# CH32V103R-R0.net
KiCad netlist of a schematic drawn in Altium Designer
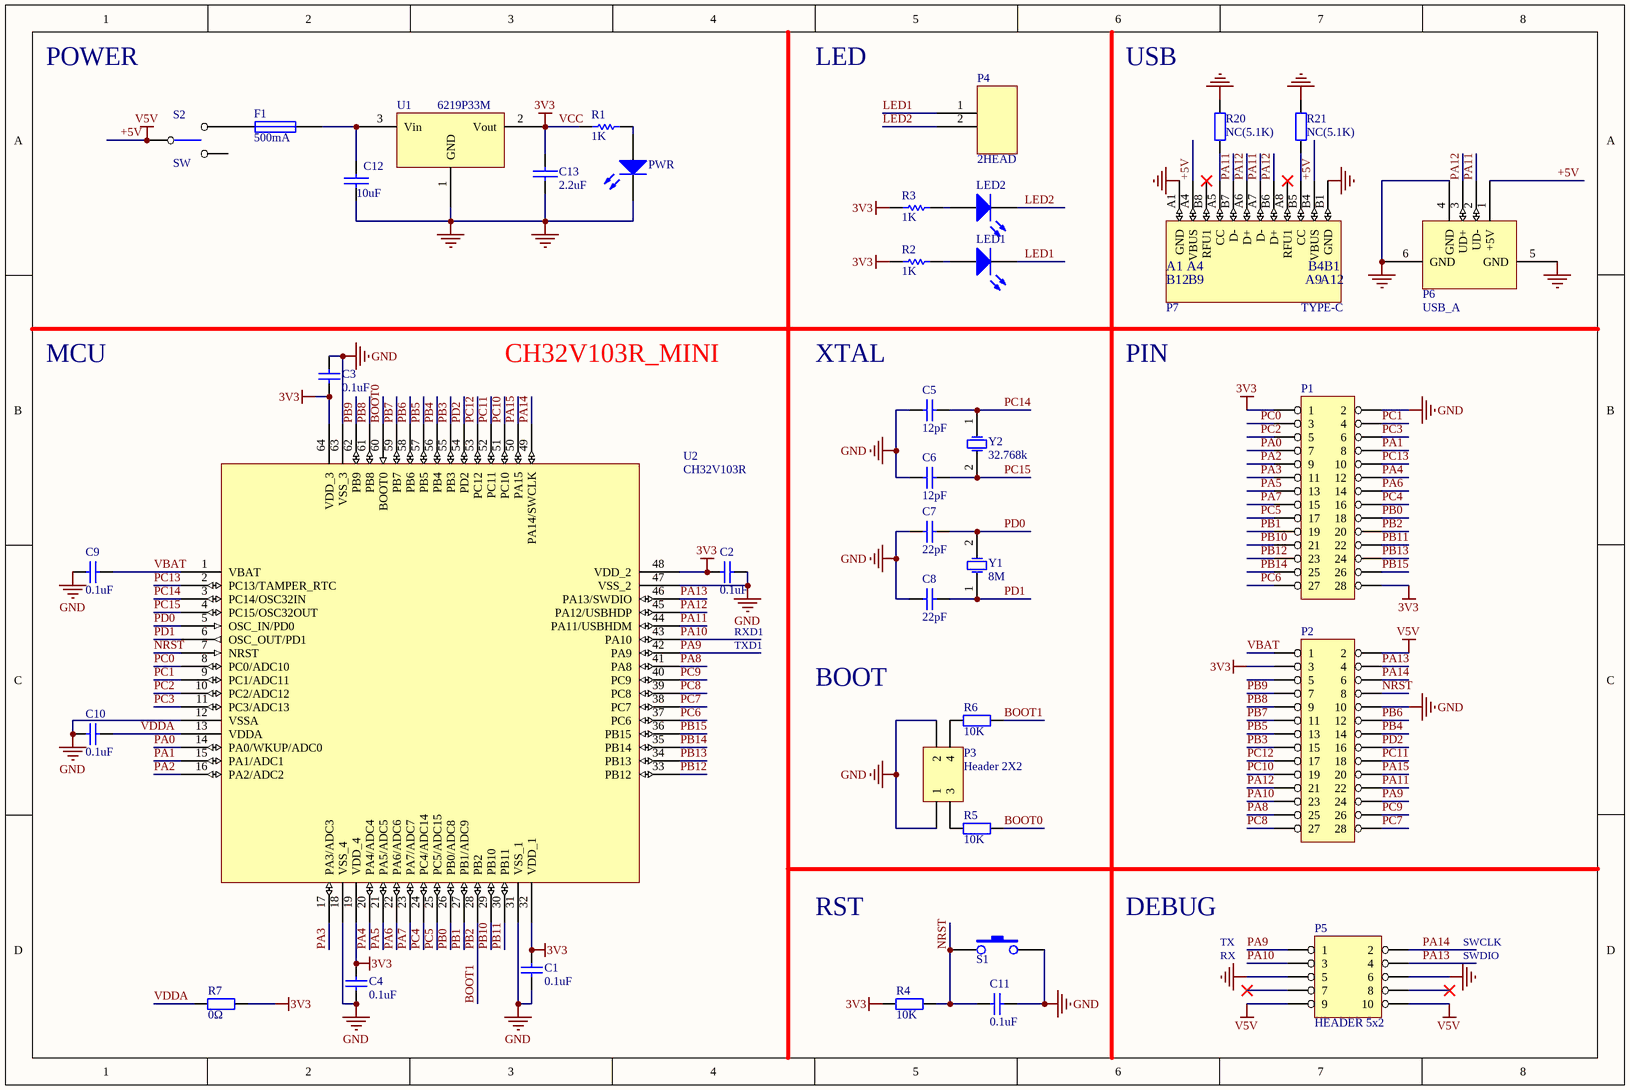
[diagram p0: CH32V103R-R0.SchDoc]

(export (version "E")
  (design (tool "Eeschema 10.0.6"))
  (components
    (comp (ref "C1")
      (value "0.1uF")
      (footprint "0603_C")
      (description "Capacitor")
      (fields (field (name "PUBLISHER") "Altium Limited"))
      (libsource (lib "Miscellaneous Devices") (part "Cap"))
    )
    (comp (ref "C2")
      (value "0.1uF")
      (footprint "0603_C")
      (description "Capacitor")
      (fields (field (name "PUBLISHER") "Altium Limited"))
      (libsource (lib "Miscellaneous Devices") (part "Cap"))
    )
    (comp (ref "C3")
      (value "0.1uF")
      (footprint "0603_C")
      (description "Capacitor")
      (fields (field (name "PUBLISHER") "Altium Limited"))
      (libsource (lib "Miscellaneous Devices") (part "Cap"))
    )
    (comp (ref "C4")
      (value "0.1uF")
      (footprint "0603_C")
      (description "Capacitor")
      (fields (field (name "PUBLISHER") "Altium Limited"))
      (libsource (lib "Miscellaneous Devices") (part "Cap"))
    )
    (comp (ref "C5")
      (value "12pF")
      (footprint "0603_C")
      (description "Capacitor")
      (fields (field (name "PUBLISHER") "Altium Limited"))
      (libsource (lib "Miscellaneous Devices") (part "Cap"))
    )
    (comp (ref "C6")
      (value "12pF")
      (footprint "0603_C")
      (description "Capacitor")
      (fields (field (name "PUBLISHER") "Altium Limited"))
      (libsource (lib "Miscellaneous Devices") (part "Cap"))
    )
    (comp (ref "C7")
      (value "22pF")
      (footprint "0603_C")
      (description "Capacitor")
      (fields (field (name "PUBLISHER") "Altium Limited"))
      (libsource (lib "Miscellaneous Devices") (part "Cap"))
    )
    (comp (ref "C8")
      (value "22pF")
      (footprint "0603_C")
      (description "Capacitor")
      (fields (field (name "PUBLISHER") "Altium Limited"))
      (libsource (lib "Miscellaneous Devices") (part "Cap"))
    )
    (comp (ref "C9")
      (value "0.1uF")
      (footprint "0603_C")
      (description "Capacitor")
      (fields (field (name "PUBLISHER") "Altium Limited"))
      (libsource (lib "Miscellaneous Devices") (part "Cap"))
    )
    (comp (ref "C10")
      (value "0.1uF")
      (footprint "0603_C")
      (description "Capacitor")
      (fields (field (name "PUBLISHER") "Altium Limited"))
      (libsource (lib "Miscellaneous Devices") (part "Cap"))
    )
    (comp (ref "C11")
      (value "0.1uF")
      (footprint "0603_C")
      (description "Capacitor")
      (fields (field (name "PUBLISHER") "Altium Limited"))
      (libsource (lib "Miscellaneous Devices") (part "Cap"))
    )
    (comp (ref "C12")
      (value "10uF")
      (footprint "3216_C")
      (description "Capacitor")
      (libsource (lib "*") (part "CAP"))
    )
    (comp (ref "C13")
      (value "2.2uF")
      (footprint "0603_C")
      (description "Capacitor")
      (libsource (lib "*") (part "CAP"))
    )
    (comp (ref "F1")
      (value "500mA")
      (footprint "0603")
      (description "Fuse")
      (libsource (lib "*") (part "FUSE1"))
    )
    (comp (ref "LED1")
      (value "LED1   blue")
      (footprint "0603+")
      (description "Typical INFRARED GaAs LED")
      (fields (field (name "PUBLISHER") "Altium Limited"))
      (libsource (lib "Miscellaneous Devices") (part "LED0"))
    )
    (comp (ref "LED2")
      (value "LED2  blue")
      (footprint "0603+")
      (description "Typical INFRARED GaAs LED")
      (fields (field (name "PUBLISHER") "Altium Limited"))
      (libsource (lib "Miscellaneous Devices") (part "LED0"))
    )
    (comp (ref "P1")
      (value "HEADER 14x2")
      (footprint "MYPCB:IDC28-2.54MM")
      (description "Header, 14-Pin, Dual row")
      (libsource (lib "wch_sch_others") (part "HEADER 14x2"))
    )
    (comp (ref "P2")
      (value "HEADER 14x2")
      (footprint "MYPCB:IDC28-2.54MM")
      (description "Header, 14-Pin, Dual row")
      (libsource (lib "wch_sch_others") (part "HEADER 14x2"))
    )
    (comp (ref "P3")
      (value "Header 2X2")
      (footprint "IDC4-2.54mm")
      (description "Header, 2-Pin, Dual row")
      (fields (field (name "PUBLISHER") "Altium Limited"))
      (libsource (lib "Miscellaneous Connectors") (part "Header 2X2"))
    )
    (comp (ref "P4") (value "2HEAD") (footprint "SIP2-2.54mm") (libsource (lib "MYSCH") (part "2HEAD")))
    (comp (ref "P5")
      (value "HEADER 5x2")
      (footprint "MYPCB:IDC10-2.54mm")
      (description "Header, 4-Pin, Dual row")
      (libsource (lib "wch_sch_others") (part "HEADER 5x2"))
    )
    (comp (ref "P6")
      (value "USB_A")
      (footprint "USBAF")
      (description "USB Port")
      (libsource (lib "CHXXXSCH") (part "USB"))
    )
    (comp (ref "P7")
      (value "TYPE-C")
      (footprint "TYPE-C-Receptacle-2.0")
      (libsource (lib "*") (part "TYPE-C1"))
    )
    (comp (ref "PWR")
      (value "POWER  red")
      (footprint "0603+")
      (description "Typical INFRARED GaAs LED")
      (fields (field (name "PUBLISHER") "Altium Limited"))
      (libsource (lib "Miscellaneous Devices") (part "LED0"))
    )
    (comp (ref "R1")
      (value "1K")
      (footprint "0603")
      (description "Semiconductor Resistor")
      (fields (field (name "PUBLISHER") "Altium Limited"))
      (libsource (lib "Miscellaneous Devices") (part "Res Semi"))
    )
    (comp (ref "R2")
      (value "1K")
      (footprint "0603")
      (description "Semiconductor Resistor")
      (fields (field (name "PUBLISHER") "Altium Limited"))
      (libsource (lib "Miscellaneous Devices") (part "Res Semi"))
    )
    (comp (ref "R3")
      (value "1K")
      (footprint "0603")
      (description "Semiconductor Resistor")
      (fields (field (name "PUBLISHER") "Altium Limited"))
      (libsource (lib "Miscellaneous Devices") (part "Res Semi"))
    )
    (comp (ref "R4")
      (value "10K")
      (footprint "0603")
      (description "Resistor")
      (fields (field (name "PUBLISHER") "Altium Limited"))
      (libsource (lib "") (part "Res2_1"))
    )
    (comp (ref "R5")
      (value "10K")
      (footprint "0603")
      (description "Resistor")
      (fields (field (name "PUBLISHER") "Altium Limited"))
      (libsource (lib "") (part "Res2_1"))
    )
    (comp (ref "R6")
      (value "10K")
      (footprint "0603")
      (description "Resistor")
      (fields (field (name "PUBLISHER") "Altium Limited"))
      (libsource (lib "") (part "Res2_1"))
    )
    (comp (ref "R7")
      (value "0Ω")
      (footprint "0603")
      (description "Resistor")
      (fields (field (name "PUBLISHER") "Altium Limited"))
      (libsource (lib "") (part "Res2_1"))
    )
    (comp (ref "R20")
      (value "NC(5.1K)")
      (footprint "0603")
      (description "Resistor")
      (libsource (lib "Miscellaneous Devices") (part "Res2"))
    )
    (comp (ref "R21")
      (value "NC(5.1K)")
      (footprint "0603")
      (description "Resistor")
      (libsource (lib "Miscellaneous Devices") (part "Res2"))
    )
    (comp (ref "S1") (value "KEY") (footprint "贴片按键") (libsource (lib "CCDXPLIB") (part "KEY")))
    (comp (ref "S2") (value "SW") (footprint "KEY2") (libsource (lib "MYSCH") (part "SW")))
    (comp (ref "U1")
      (value "6219P33M")
      (footprint "SOT-23")
      (libsource (lib "wch_sch_others") (part "6219P33M"))
    )
    (comp (ref "U2")
      (value "CH32V103R")
      (footprint "LQFP64M_10X10")
      (description "RISC-V MCU with USB device & USB host & ADC & Touch Key")
      (libsource (lib "CHXXX") (part "CH32V103R"))
    )
    (comp (ref "Y1")
      (value "8M")
      (footprint "XT_AT49")
      (description "Crystal Oscillator")
      (fields (field (name "PUBLISHER") "Altium Limited"))
      (libsource (lib "Miscellaneous Devices") (part "XTAL"))
    )
    (comp (ref "Y2")
      (value "32.768k")
      (footprint "FC-135")
      (description "Crystal Oscillator")
      (fields (field (name "PUBLISHER") "Altium Limited"))
      (libsource (lib "Miscellaneous Devices") (part "XTAL"))
    )
  )
  (nets
    (net (code "2") (name "/BOOT0") (class "Default")
      (node (ref "R5") (pin "1") (pinfunction "1_1") (pintype "passive"))
      (node (ref "U2") (pin "60") (pinfunction "BOOT0_60") (pintype "input"))
    )
    (net (code "3") (name "/BOOT1") (class "Default")
      (node (ref "P1") (pin "20") (pinfunction "20_20") (pintype "passive"))
      (node (ref "R6") (pin "1") (pinfunction "1_1") (pintype "passive"))
      (node (ref "U2") (pin "28") (pinfunction "PB2_28") (pintype "bidirectional"))
    )
    (net (code "4") (name "/LED1") (class "Default")
      (node (ref "LED1") (pin "2") (pinfunction "K_2") (pintype "passive"))
      (node (ref "P4") (pin "1") (pintype "passive"))
    )
    (net (code "5") (name "/LED2") (class "Default")
      (node (ref "LED2") (pin "2") (pinfunction "K_2") (pintype "passive"))
      (node (ref "P4") (pin "2") (pintype "passive"))
    )
    (net (code "6") (name "/NRST") (class "Default")
      (node (ref "C11") (pin "2") (pinfunction "2_2") (pintype "passive"))
      (node (ref "P2") (pin "8") (pinfunction "8_8") (pintype "passive"))
      (node (ref "R4") (pin "1") (pinfunction "1_1") (pintype "passive"))
      (node (ref "S1") (pin "1") (pinfunction "1_1") (pintype "passive"))
      (node (ref "U2") (pin "7") (pinfunction "NRST_7") (pintype "input"))
    )
    (net (code "7") (name "/PA0") (class "Default")
      (node (ref "P1") (pin "7") (pinfunction "7_7") (pintype "passive"))
      (node (ref "U2") (pin "14") (pinfunction "PA0/WKUP/ADC0_14") (pintype "bidirectional"))
    )
    (net (code "8") (name "/PA1") (class "Default")
      (node (ref "P1") (pin "8") (pinfunction "8_8") (pintype "passive"))
      (node (ref "U2") (pin "15") (pinfunction "PA1/ADC1_15") (pintype "bidirectional"))
    )
    (net (code "9") (name "/PA2") (class "Default")
      (node (ref "P1") (pin "9") (pinfunction "9_9") (pintype "passive"))
      (node (ref "U2") (pin "16") (pinfunction "PA2/ADC2_16") (pintype "bidirectional"))
    )
    (net (code "10") (name "/PA3") (class "Default")
      (node (ref "P1") (pin "11") (pinfunction "11_11") (pintype "passive"))
      (node (ref "U2") (pin "17") (pinfunction "PA3/ADC3_17") (pintype "bidirectional"))
    )
    (net (code "11") (name "/PA4") (class "Default")
      (node (ref "P1") (pin "12") (pinfunction "12_12") (pintype "passive"))
      (node (ref "U2") (pin "20") (pinfunction "PA4/ADC4_20") (pintype "bidirectional"))
    )
    (net (code "12") (name "/PA5") (class "Default")
      (node (ref "P1") (pin "13") (pinfunction "13_13") (pintype "passive"))
      (node (ref "U2") (pin "21") (pinfunction "PA5/ADC5_21") (pintype "bidirectional"))
    )
    (net (code "13") (name "/PA6") (class "Default")
      (node (ref "P1") (pin "14") (pinfunction "14_14") (pintype "passive"))
      (node (ref "U2") (pin "22") (pinfunction "PA6/ADC6_22") (pintype "bidirectional"))
    )
    (net (code "14") (name "/PA7") (class "Default")
      (node (ref "P1") (pin "15") (pinfunction "15_15") (pintype "passive"))
      (node (ref "U2") (pin "23") (pinfunction "PA7/ADC7_23") (pintype "bidirectional"))
    )
    (net (code "15") (name "/PA8") (class "Default")
      (node (ref "P2") (pin "25") (pinfunction "25_25") (pintype "passive"))
      (node (ref "U2") (pin "41") (pinfunction "PA8_41") (pintype "bidirectional"))
    )
    (net (code "16") (name "/PA9") (class "Default")
      (node (ref "P2") (pin "24") (pinfunction "24_24") (pintype "passive"))
      (node (ref "P5") (pin "1") (pinfunction "1_1") (pintype "passive"))
      (node (ref "U2") (pin "42") (pinfunction "PA9_42") (pintype "bidirectional"))
    )
    (net (code "17") (name "/PA10") (class "Default")
      (node (ref "P2") (pin "23") (pinfunction "23_23") (pintype "passive"))
      (node (ref "P5") (pin "3") (pinfunction "3_3") (pintype "passive"))
      (node (ref "U2") (pin "43") (pinfunction "PA10_43") (pintype "bidirectional"))
    )
    (net (code "18") (name "/PA11") (class "Default")
      (node (ref "P2") (pin "22") (pinfunction "22_22") (pintype "passive"))
      (node (ref "P6") (pin "2") (pinfunction "UD-_2") (pintype "bidirectional"))
      (node (ref "P7") (pin "A7") (pinfunction "D-_A7") (pintype "bidirectional"))
      (node (ref "P7") (pin "B7") (pinfunction "D-_B7") (pintype "bidirectional"))
      (node (ref "U2") (pin "44") (pinfunction "PA11/USBHDM_44") (pintype "bidirectional"))
    )
    (net (code "19") (name "/PA12") (class "Default")
      (node (ref "P2") (pin "21") (pinfunction "21_21") (pintype "passive"))
      (node (ref "P6") (pin "3") (pinfunction "UD+_3") (pintype "bidirectional"))
      (node (ref "P7") (pin "A6") (pinfunction "D+_A6") (pintype "bidirectional"))
      (node (ref "P7") (pin "B6") (pinfunction "D+_B6") (pintype "bidirectional"))
      (node (ref "U2") (pin "45") (pinfunction "PA12/USBHDP_45") (pintype "bidirectional"))
    )
    (net (code "20") (name "/PA13") (class "Default")
      (node (ref "P2") (pin "4") (pinfunction "4_4") (pintype "passive"))
      (node (ref "P5") (pin "4") (pinfunction "4_4") (pintype "passive"))
      (node (ref "U2") (pin "46") (pinfunction "PA13/SWDIO_46") (pintype "bidirectional"))
    )
    (net (code "21") (name "/PA14") (class "Default")
      (node (ref "P2") (pin "6") (pinfunction "6_6") (pintype "passive"))
      (node (ref "P5") (pin "2") (pinfunction "2_2") (pintype "passive"))
      (node (ref "U2") (pin "49") (pinfunction "PA14/SWCLK_49") (pintype "bidirectional"))
    )
    (net (code "22") (name "/PA15") (class "Default")
      (node (ref "P2") (pin "20") (pinfunction "20_20") (pintype "passive"))
      (node (ref "U2") (pin "50") (pinfunction "PA15_50") (pintype "bidirectional"))
    )
    (net (code "23") (name "/PB0") (class "Default")
      (node (ref "P1") (pin "18") (pinfunction "18_18") (pintype "passive"))
      (node (ref "U2") (pin "26") (pinfunction "PB0/ADC8_26") (pintype "bidirectional"))
    )
    (net (code "24") (name "/PB1") (class "Default")
      (node (ref "P1") (pin "19") (pinfunction "19_19") (pintype "passive"))
      (node (ref "U2") (pin "27") (pinfunction "PB1/ADC9_27") (pintype "bidirectional"))
    )
    (net (code "25") (name "/PB3") (class "Default")
      (node (ref "P2") (pin "15") (pinfunction "15_15") (pintype "passive"))
      (node (ref "U2") (pin "55") (pinfunction "PB3_55") (pintype "bidirectional"))
    )
    (net (code "26") (name "/PB4") (class "Default")
      (node (ref "P2") (pin "14") (pinfunction "14_14") (pintype "passive"))
      (node (ref "U2") (pin "56") (pinfunction "PB4_56") (pintype "bidirectional"))
    )
    (net (code "27") (name "/PB5") (class "Default")
      (node (ref "P2") (pin "13") (pinfunction "13_13") (pintype "passive"))
      (node (ref "U2") (pin "57") (pinfunction "PB5_57") (pintype "bidirectional"))
    )
    (net (code "28") (name "/PB6") (class "Default")
      (node (ref "P2") (pin "12") (pinfunction "12_12") (pintype "passive"))
      (node (ref "U2") (pin "58") (pinfunction "PB6_58") (pintype "bidirectional"))
    )
    (net (code "29") (name "/PB7") (class "Default")
      (node (ref "P2") (pin "11") (pinfunction "11_11") (pintype "passive"))
      (node (ref "U2") (pin "59") (pinfunction "PB7_59") (pintype "bidirectional"))
    )
    (net (code "30") (name "/PB8") (class "Default")
      (node (ref "P2") (pin "9") (pinfunction "9_9") (pintype "passive"))
      (node (ref "U2") (pin "61") (pinfunction "PB8_61") (pintype "bidirectional"))
    )
    (net (code "31") (name "/PB9") (class "Default")
      (node (ref "P2") (pin "7") (pinfunction "7_7") (pintype "passive"))
      (node (ref "U2") (pin "62") (pinfunction "PB9_62") (pintype "bidirectional"))
    )
    (net (code "32") (name "/PB10") (class "Default")
      (node (ref "P1") (pin "21") (pinfunction "21_21") (pintype "passive"))
      (node (ref "U2") (pin "29") (pinfunction "PB10_29") (pintype "bidirectional"))
    )
    (net (code "33") (name "/PB11") (class "Default")
      (node (ref "P1") (pin "22") (pinfunction "22_22") (pintype "passive"))
      (node (ref "U2") (pin "30") (pinfunction "PB11_30") (pintype "bidirectional"))
    )
    (net (code "34") (name "/PB12") (class "Default")
      (node (ref "P1") (pin "23") (pinfunction "23_23") (pintype "passive"))
      (node (ref "U2") (pin "33") (pinfunction "PB12_33") (pintype "bidirectional"))
    )
    (net (code "35") (name "/PB13") (class "Default")
      (node (ref "P1") (pin "24") (pinfunction "24_24") (pintype "passive"))
      (node (ref "U2") (pin "34") (pinfunction "PB13_34") (pintype "bidirectional"))
    )
    (net (code "36") (name "/PB14") (class "Default")
      (node (ref "P1") (pin "25") (pinfunction "25_25") (pintype "passive"))
      (node (ref "U2") (pin "35") (pinfunction "PB14_35") (pintype "bidirectional"))
    )
    (net (code "37") (name "/PB15") (class "Default")
      (node (ref "P1") (pin "26") (pinfunction "26_26") (pintype "passive"))
      (node (ref "U2") (pin "36") (pinfunction "PB15_36") (pintype "bidirectional"))
    )
    (net (code "38") (name "/PC0") (class "Default")
      (node (ref "P1") (pin "3") (pinfunction "3_3") (pintype "passive"))
      (node (ref "U2") (pin "8") (pinfunction "PC0/ADC10_8") (pintype "bidirectional"))
    )
    (net (code "39") (name "/PC1") (class "Default")
      (node (ref "P1") (pin "4") (pinfunction "4_4") (pintype "passive"))
      (node (ref "U2") (pin "9") (pinfunction "PC1/ADC11_9") (pintype "bidirectional"))
    )
    (net (code "40") (name "/PC2") (class "Default")
      (node (ref "P1") (pin "5") (pinfunction "5_5") (pintype "passive"))
      (node (ref "U2") (pin "10") (pinfunction "PC2/ADC12_10") (pintype "bidirectional"))
    )
    (net (code "41") (name "/PC3") (class "Default")
      (node (ref "P1") (pin "6") (pinfunction "6_6") (pintype "passive"))
      (node (ref "U2") (pin "11") (pinfunction "PC3/ADC13_11") (pintype "bidirectional"))
    )
    (net (code "42") (name "/PC4") (class "Default")
      (node (ref "P1") (pin "16") (pinfunction "16_16") (pintype "passive"))
      (node (ref "U2") (pin "24") (pinfunction "PC4/ADC14_24") (pintype "bidirectional"))
    )
    (net (code "43") (name "/PC5") (class "Default")
      (node (ref "P1") (pin "17") (pinfunction "17_17") (pintype "passive"))
      (node (ref "U2") (pin "25") (pinfunction "PC5/ADC15_25") (pintype "bidirectional"))
    )
    (net (code "44") (name "/PC6") (class "Default")
      (node (ref "P1") (pin "27") (pinfunction "27_27") (pintype "passive"))
      (node (ref "U2") (pin "37") (pinfunction "PC6_37") (pintype "bidirectional"))
    )
    (net (code "45") (name "/PC7") (class "Default")
      (node (ref "P2") (pin "28") (pinfunction "28_28") (pintype "passive"))
      (node (ref "U2") (pin "38") (pinfunction "PC7_38") (pintype "bidirectional"))
    )
    (net (code "46") (name "/PC8") (class "Default")
      (node (ref "P2") (pin "27") (pinfunction "27_27") (pintype "passive"))
      (node (ref "U2") (pin "39") (pinfunction "PC8_39") (pintype "bidirectional"))
    )
    (net (code "47") (name "/PC9") (class "Default")
      (node (ref "P2") (pin "26") (pinfunction "26_26") (pintype "passive"))
      (node (ref "U2") (pin "40") (pinfunction "PC9_40") (pintype "bidirectional"))
    )
    (net (code "48") (name "/PC10") (class "Default")
      (node (ref "P2") (pin "19") (pinfunction "19_19") (pintype "passive"))
      (node (ref "U2") (pin "51") (pinfunction "PC10_51") (pintype "bidirectional"))
    )
    (net (code "49") (name "/PC11") (class "Default")
      (node (ref "P2") (pin "18") (pinfunction "18_18") (pintype "passive"))
      (node (ref "U2") (pin "52") (pinfunction "PC11_52") (pintype "bidirectional"))
    )
    (net (code "50") (name "/PC12") (class "Default")
      (node (ref "P2") (pin "17") (pinfunction "17_17") (pintype "passive"))
      (node (ref "U2") (pin "53") (pinfunction "PC12_53") (pintype "bidirectional"))
    )
    (net (code "51") (name "/PC13") (class "Default")
      (node (ref "P1") (pin "10") (pinfunction "10_10") (pintype "passive"))
      (node (ref "U2") (pin "2") (pinfunction "PC13/TAMPER_RTC_2") (pintype "bidirectional"))
    )
    (net (code "52") (name "/PC14") (class "Default")
      (node (ref "C5") (pin "1") (pinfunction "1_1") (pintype "passive"))
      (node (ref "U2") (pin "3") (pinfunction "PC14/OSC32IN_3") (pintype "bidirectional"))
      (node (ref "Y2") (pin "1") (pinfunction "OSC1_1") (pintype "passive"))
    )
    (net (code "53") (name "/PC15") (class "Default")
      (node (ref "C6") (pin "1") (pinfunction "1_1") (pintype "passive"))
      (node (ref "U2") (pin "4") (pinfunction "PC15/OSC32OUT_4") (pintype "bidirectional"))
      (node (ref "Y2") (pin "2") (pinfunction "OSC2_2") (pintype "passive"))
    )
    (net (code "54") (name "/PD0") (class "Default")
      (node (ref "C7") (pin "2") (pinfunction "2_2") (pintype "passive"))
      (node (ref "U2") (pin "5") (pinfunction "OSC_IN/PD0_5") (pintype "input"))
      (node (ref "Y1") (pin "2") (pinfunction "OSC2_2") (pintype "passive"))
    )
    (net (code "55") (name "/PD1") (class "Default")
      (node (ref "C8") (pin "2") (pinfunction "2_2") (pintype "passive"))
      (node (ref "U2") (pin "6") (pinfunction "OSC_OUT/PD1_6") (pintype "output"))
      (node (ref "Y1") (pin "1") (pinfunction "OSC1_1") (pintype "passive"))
    )
    (net (code "56") (name "/PD2") (class "Default")
      (node (ref "P2") (pin "16") (pinfunction "16_16") (pintype "passive"))
      (node (ref "U2") (pin "54") (pinfunction "PD2_54") (pintype "bidirectional"))
    )
    (net (code "57") (name "/VBAT") (class "Default")
      (node (ref "C9") (pin "1") (pinfunction "1_1") (pintype "passive"))
      (node (ref "P2") (pin "1") (pinfunction "1_1") (pintype "passive"))
      (node (ref "U2") (pin "1") (pinfunction "VBAT_1") (pintype "power_in"))
    )
    (net (code "58") (name "/VDDA") (class "Default")
      (node (ref "C10") (pin "1") (pinfunction "1_1") (pintype "passive"))
      (node (ref "R7") (pin "2") (pinfunction "2_2") (pintype "passive"))
      (node (ref "U2") (pin "13") (pinfunction "VDDA_13") (pintype "power_in"))
    )
    (net (code "59") (name "3V3") (class "Default")
      (node (ref "C1") (pin "2") (pinfunction "2_2") (pintype "passive"))
      (node (ref "C13") (pin "1") (pinfunction "1_1") (pintype "passive"))
      (node (ref "C2") (pin "2") (pinfunction "2_2") (pintype "passive"))
      (node (ref "C3") (pin "2") (pinfunction "2_2") (pintype "passive"))
      (node (ref "C4") (pin "2") (pinfunction "2_2") (pintype "passive"))
      (node (ref "P1") (pin "1") (pinfunction "1_1") (pintype "passive"))
      (node (ref "P1") (pin "28") (pinfunction "28_28") (pintype "passive"))
      (node (ref "P2") (pin "3") (pinfunction "3_3") (pintype "passive"))
      (node (ref "R1") (pin "2") (pinfunction "2_2") (pintype "passive"))
      (node (ref "R2") (pin "1") (pinfunction "1_1") (pintype "passive"))
      (node (ref "R3") (pin "1") (pinfunction "1_1") (pintype "passive"))
      (node (ref "R4") (pin "2") (pinfunction "2_2") (pintype "passive"))
      (node (ref "R7") (pin "1") (pinfunction "1_1") (pintype "passive"))
      (node (ref "U1") (pin "2") (pinfunction "Vout_2") (pintype "passive"))
      (node (ref "U2") (pin "19") (pinfunction "VDD_4_19") (pintype "power_in"))
      (node (ref "U2") (pin "32") (pinfunction "VDD_1_32") (pintype "power_in"))
      (node (ref "U2") (pin "48") (pinfunction "VDD_2_48") (pintype "power_in"))
      (node (ref "U2") (pin "64") (pinfunction "VDD_3_64") (pintype "power_in"))
    )
    (net (code "60") (name "GND") (class "Default")
      (node (ref "C1") (pin "1") (pinfunction "1_1") (pintype "passive"))
      (node (ref "C10") (pin "2") (pinfunction "2_2") (pintype "passive"))
      (node (ref "C11") (pin "1") (pinfunction "1_1") (pintype "passive"))
      (node (ref "C12") (pin "2") (pinfunction "2_2") (pintype "passive"))
      (node (ref "C13") (pin "2") (pinfunction "2_2") (pintype "passive"))
      (node (ref "C2") (pin "1") (pinfunction "1_1") (pintype "passive"))
      (node (ref "C3") (pin "1") (pinfunction "1_1") (pintype "passive"))
      (node (ref "C4") (pin "1") (pinfunction "1_1") (pintype "passive"))
      (node (ref "C5") (pin "2") (pinfunction "2_2") (pintype "passive"))
      (node (ref "C6") (pin "2") (pinfunction "2_2") (pintype "passive"))
      (node (ref "C7") (pin "1") (pinfunction "1_1") (pintype "passive"))
      (node (ref "C8") (pin "1") (pinfunction "1_1") (pintype "passive"))
      (node (ref "C9") (pin "2") (pinfunction "2_2") (pintype "passive"))
      (node (ref "P1") (pin "2") (pinfunction "2_2") (pintype "passive"))
      (node (ref "P2") (pin "10") (pinfunction "10_10") (pintype "passive"))
      (node (ref "P3") (pin "1") (pinfunction "1_1") (pintype "passive"))
      (node (ref "P3") (pin "2") (pinfunction "2_2") (pintype "passive"))
      (node (ref "P5") (pin "5") (pinfunction "5_5") (pintype "passive"))
      (node (ref "P5") (pin "6") (pinfunction "6_6") (pintype "passive"))
      (node (ref "P6") (pin "4") (pinfunction "GND_4") (pintype "power_in"))
      (node (ref "P6") (pin "5") (pinfunction "GND_5") (pintype "power_in"))
      (node (ref "P6") (pin "6") (pinfunction "GND_6") (pintype "power_in"))
      (node (ref "P7") (pin "A1") (pinfunction "GND_A1") (pintype "bidirectional"))
      (node (ref "P7") (pin "B1") (pinfunction "GND_B1") (pintype "bidirectional"))
      (node (ref "PWR") (pin "2") (pinfunction "K_2") (pintype "passive"))
      (node (ref "R20") (pin "2") (pinfunction "2_2") (pintype "passive"))
      (node (ref "R21") (pin "2") (pinfunction "2_2") (pintype "passive"))
      (node (ref "S1") (pin "3") (pinfunction "3_3") (pintype "passive"))
      (node (ref "U1") (pin "1") (pinfunction "GND_1") (pintype "passive"))
      (node (ref "U2") (pin "12") (pinfunction "VSSA_12") (pintype "power_in"))
      (node (ref "U2") (pin "18") (pinfunction "VSS_4_18") (pintype "power_in"))
      (node (ref "U2") (pin "31") (pinfunction "VSS_1_31") (pintype "power_in"))
      (node (ref "U2") (pin "47") (pinfunction "VSS_2_47") (pintype "power_in"))
      (node (ref "U2") (pin "63") (pinfunction "VSS_3_63") (pintype "power_in"))
    )
    (net (code "61") (name "Net-(F1-Pad1)") (class "Default")
      (node (ref "F1") (pin "1") (pinfunction "1_1") (pintype "passive"))
      (node (ref "S2") (pin "3") (pinfunction "3_3") (pintype "passive"))
    )
    (net (code "62") (name "Net-(LED1-A)") (class "Default")
      (node (ref "LED1") (pin "1") (pinfunction "A_1") (pintype "passive"))
      (node (ref "R2") (pin "2") (pinfunction "2_2") (pintype "passive"))
    )
    (net (code "63") (name "Net-(LED2-A)") (class "Default")
      (node (ref "LED2") (pin "1") (pinfunction "A_1") (pintype "passive"))
      (node (ref "R3") (pin "2") (pinfunction "2_2") (pintype "passive"))
    )
    (net (code "64") (name "Net-(P3-Pad3)") (class "Default")
      (node (ref "P3") (pin "3") (pinfunction "3_3") (pintype "passive"))
      (node (ref "R5") (pin "2") (pinfunction "2_2") (pintype "passive"))
    )
    (net (code "65") (name "Net-(P3-Pad4)") (class "Default")
      (node (ref "P3") (pin "4") (pinfunction "4_4") (pintype "passive"))
      (node (ref "R6") (pin "2") (pinfunction "2_2") (pintype "passive"))
    )
    (net (code "66") (name "Net-(P7-CC-PadA5)") (class "Default")
      (node (ref "P7") (pin "A5") (pinfunction "CC_A5") (pintype "bidirectional"))
      (node (ref "R20") (pin "1") (pinfunction "1_1") (pintype "passive"))
    )
    (net (code "67") (name "Net-(P7-CC-PadB5)") (class "Default")
      (node (ref "P7") (pin "B5") (pinfunction "CC_B5") (pintype "bidirectional"))
      (node (ref "R21") (pin "1") (pinfunction "1_1") (pintype "passive"))
    )
    (net (code "68") (name "Net-(PWR-A)") (class "Default")
      (node (ref "PWR") (pin "1") (pinfunction "A_1") (pintype "passive"))
      (node (ref "R1") (pin "1") (pinfunction "1_1") (pintype "passive"))
    )
    (net (code "69") (name "Net-(U1-Vin)") (class "Default")
      (node (ref "C12") (pin "1") (pinfunction "1_1") (pintype "passive"))
      (node (ref "F1") (pin "2") (pinfunction "2_2") (pintype "passive"))
      (node (ref "U1") (pin "3") (pinfunction "Vin_3") (pintype "passive"))
    )
    (net (code "70") (name "V5V") (class "Default")
      (node (ref "P2") (pin "2") (pinfunction "2_2") (pintype "passive"))
      (node (ref "P5") (pin "10") (pinfunction "10_10") (pintype "passive"))
      (node (ref "P5") (pin "9") (pinfunction "9_9") (pintype "passive"))
      (node (ref "P6") (pin "1") (pinfunction "+5V_1") (pintype "power_in"))
      (node (ref "P7") (pin "A4") (pinfunction "VBUS_A4") (pintype "bidirectional"))
      (node (ref "P7") (pin "B4") (pinfunction "VBUS_B4") (pintype "bidirectional"))
      (node (ref "S2") (pin "1") (pinfunction "1_1") (pintype "passive"))
    )
    (net (code "71") (name "unconnected-(P2-Pad5)") (class "Default")
      (node (ref "P2") (pin "5") (pinfunction "5_5") (pintype "passive"))
    )
    (net (code "72") (name "unconnected-(P5-Pad7)") (class "Default")
      (node (ref "P5") (pin "7") (pinfunction "7_7") (pintype "passive+no_connect"))
    )
    (net (code "73") (name "unconnected-(P5-Pad8)") (class "Default")
      (node (ref "P5") (pin "8") (pinfunction "8_8") (pintype "passive+no_connect"))
    )
    (net (code "74") (name "unconnected-(P7-RFU1-PadA8)") (class "Default")
      (node (ref "P7") (pin "A8") (pinfunction "RFU1_A8") (pintype "bidirectional+no_connect"))
    )
    (net (code "75") (name "unconnected-(P7-RFU1-PadB8)") (class "Default")
      (node (ref "P7") (pin "B8") (pinfunction "RFU1_B8") (pintype "bidirectional+no_connect"))
    )
    (net (code "76") (name "unconnected-(S2-Pad2)") (class "Default")
      (node (ref "S2") (pin "2") (pinfunction "2_2") (pintype "passive"))
    )
  )
)
